# Az_Proj.net
KiCad netlist of a schematic drawn in Altium Designer
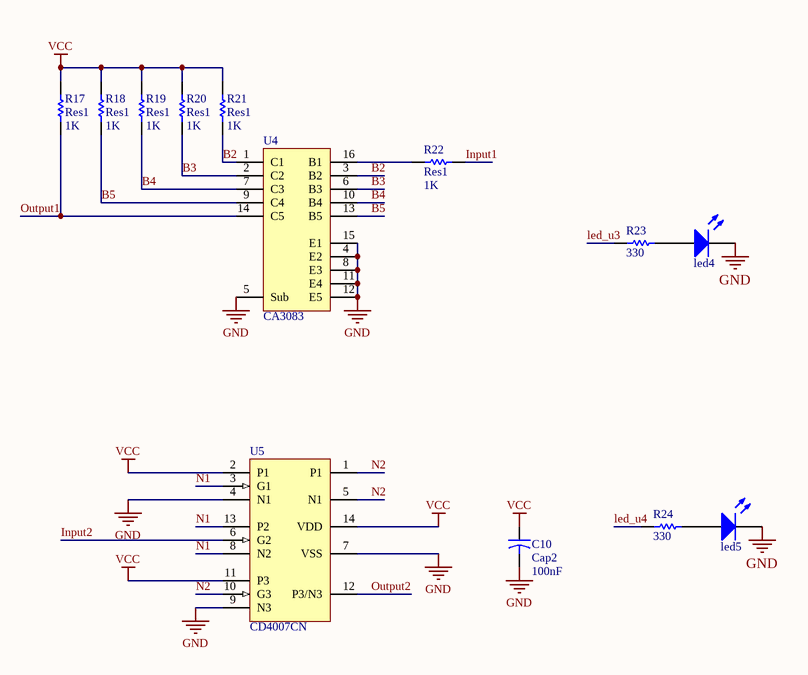
[diagram p0: Az_Proj.SchDoc]

(export (version "E")
  (design (tool "Eeschema 10.0.6"))
  (components
    (comp (ref "C10")
      (value "Cap2")
      (footprint "My_cap100n")
      (description "Capacitor")
      (fields (field (name "ALTIUM_VALUE") "100nF") (field (name "PUBLISHER") "Altium Limited"))
      (libsource (lib "Miscellaneous Devices") (part "Cap2"))
    )
    (comp (ref "led4")
      (value "LED 5mm")
      (footprint "Mine-Discreet:LED-5mm")
      (description "Typical LED")
      (fields (field (name "DESIGNER") "Seyed Mohsen Ghasemian") (field (name "PUBLISHER") "www.picpars.com"))
      (libsource (lib "PicPars.com_usefully_Library") (part "LED 5mm"))
    )
    (comp (ref "led5")
      (value "LED 5mm")
      (footprint "Mine-Discreet:LED-5mm")
      (description "Typical LED")
      (fields (field (name "DESIGNER") "Seyed Mohsen Ghasemian") (field (name "PUBLISHER") "www.picpars.com"))
      (libsource (lib "PicPars.com_usefully_Library") (part "LED 5mm"))
    )
    (comp (ref "R17")
      (value "Res1")
      (footprint "AXIAL-0.3")
      (description "Resistor")
      (fields (field (name "ALTIUM_VALUE") "1K") (field (name "PUBLISHER") "Altium Limited"))
      (libsource (lib "Miscellaneous Devices") (part "Res1"))
    )
    (comp (ref "R18")
      (value "Res1")
      (footprint "AXIAL-0.3")
      (description "Resistor")
      (fields (field (name "ALTIUM_VALUE") "1K") (field (name "PUBLISHER") "Altium Limited"))
      (libsource (lib "Miscellaneous Devices") (part "Res1"))
    )
    (comp (ref "R19")
      (value "Res1")
      (footprint "AXIAL-0.3")
      (description "Resistor")
      (fields (field (name "ALTIUM_VALUE") "1K") (field (name "PUBLISHER") "Altium Limited"))
      (libsource (lib "Miscellaneous Devices") (part "Res1"))
    )
    (comp (ref "R20")
      (value "Res1")
      (footprint "AXIAL-0.3")
      (description "Resistor")
      (fields (field (name "ALTIUM_VALUE") "1K") (field (name "PUBLISHER") "Altium Limited"))
      (libsource (lib "Miscellaneous Devices") (part "Res1"))
    )
    (comp (ref "R21")
      (value "Res1")
      (footprint "AXIAL-0.3")
      (description "Resistor")
      (fields (field (name "ALTIUM_VALUE") "1K") (field (name "PUBLISHER") "Altium Limited"))
      (libsource (lib "Miscellaneous Devices") (part "Res1"))
    )
    (comp (ref "R22")
      (value "Res1")
      (footprint "AXIAL-0.3")
      (description "Resistor")
      (fields (field (name "ALTIUM_VALUE") "1K") (field (name "PUBLISHER") "Altium Limited"))
      (libsource (lib "Miscellaneous Devices") (part "Res1"))
    )
    (comp (ref "R23")
      (value "330")
      (footprint "AXIAL-0.3")
      (description "Resistor")
      (fields (field (name "Comment") "Res1") (field (name "PUBLISHER") "Altium Limited"))
      (libsource (lib "Miscellaneous Devices") (part "Res1"))
    )
    (comp (ref "R24")
      (value "330")
      (footprint "AXIAL-0.3")
      (description "Resistor")
      (fields (field (name "Comment") "Res1") (field (name "PUBLISHER") "Altium Limited"))
      (libsource (lib "Miscellaneous Devices") (part "Res1"))
    )
    (comp (ref "U4") (value "CA3083") (footprint "DIP16") (libsource (lib "Ahmad_Library") (part "CA3083")))
    (comp (ref "U5")
      (value "CD4007CN")
      (footprint "DIP14")
      (description "Dual Complementary Pair Plus Inverter")
      (fields (field (name "PUBLISHER") "Altium Limited"))
      (libsource (lib "FSC Logic Switch") (part "CD4007CN"))
    )
  )
  (nets
    (net (code "1") (name "/B2") (class "Default")
      (node (ref "R21") (pin "1") (pinfunction "1_1") (pintype "passive"))
      (node (ref "U4") (pin "1") (pinfunction "C1_1") (pintype "passive"))
      (node (ref "U4") (pin "3") (pinfunction "B2_3") (pintype "passive"))
    )
    (net (code "2") (name "/B3") (class "Default")
      (node (ref "R20") (pin "1") (pinfunction "1_1") (pintype "passive"))
      (node (ref "U4") (pin "2") (pinfunction "C2_2") (pintype "passive"))
      (node (ref "U4") (pin "6") (pinfunction "B3_6") (pintype "passive"))
    )
    (net (code "3") (name "/B4") (class "Default")
      (node (ref "R19") (pin "1") (pinfunction "1_1") (pintype "passive"))
      (node (ref "U4") (pin "10") (pinfunction "B4_10") (pintype "passive"))
      (node (ref "U4") (pin "7") (pinfunction "C3_7") (pintype "passive"))
    )
    (net (code "4") (name "/B5") (class "Default")
      (node (ref "R18") (pin "1") (pinfunction "1_1") (pintype "passive"))
      (node (ref "U4") (pin "13") (pinfunction "B5_13") (pintype "passive"))
      (node (ref "U4") (pin "9") (pinfunction "C4_9") (pintype "passive"))
    )
    (net (code "5") (name "/Input1") (class "Default")
      (node (ref "R22") (pin "2") (pinfunction "2_2") (pintype "passive"))
    )
    (net (code "6") (name "/Input2") (class "Default")
      (node (ref "U5") (pin "6") (pinfunction "G2_6") (pintype "input"))
    )
    (net (code "7") (name "/N1") (class "Default")
      (node (ref "U5") (pin "13") (pinfunction "P2_13") (pintype "passive"))
      (node (ref "U5") (pin "3") (pinfunction "G1_3") (pintype "input"))
      (node (ref "U5") (pin "8") (pinfunction "N2_8") (pintype "passive"))
    )
    (net (code "8") (name "/N2") (class "Default")
      (node (ref "U5") (pin "1") (pinfunction "P1_1") (pintype "passive"))
      (node (ref "U5") (pin "10") (pinfunction "G3_10") (pintype "input"))
      (node (ref "U5") (pin "5") (pinfunction "N1_5") (pintype "passive"))
    )
    (net (code "9") (name "/Output1") (class "Default")
      (node (ref "R17") (pin "1") (pinfunction "1_1") (pintype "passive"))
      (node (ref "U4") (pin "14") (pinfunction "C5_14") (pintype "passive"))
    )
    (net (code "10") (name "/Output2") (class "Default")
      (node (ref "U5") (pin "12") (pinfunction "P3/N3_12") (pintype "passive"))
    )
    (net (code "11") (name "/led_u3") (class "Default")
      (node (ref "R23") (pin "1") (pinfunction "1_1") (pintype "passive"))
    )
    (net (code "12") (name "/led_u4") (class "Default")
      (node (ref "R24") (pin "1") (pinfunction "1_1") (pintype "passive"))
    )
    (net (code "13") (name "GND") (class "Default")
      (node (ref "C10") (pin "2") (pinfunction "2_2") (pintype "passive"))
      (node (ref "U4") (pin "11") (pinfunction "E4_11") (pintype "passive"))
      (node (ref "U4") (pin "12") (pinfunction "E5_12") (pintype "passive"))
      (node (ref "U4") (pin "15") (pinfunction "E1_15") (pintype "passive"))
      (node (ref "U4") (pin "4") (pinfunction "E2_4") (pintype "passive"))
      (node (ref "U4") (pin "5") (pinfunction "Sub_5") (pintype "passive"))
      (node (ref "U4") (pin "8") (pinfunction "E3_8") (pintype "passive"))
      (node (ref "U5") (pin "4") (pinfunction "N1_4") (pintype "passive"))
      (node (ref "U5") (pin "7") (pinfunction "VSS_7") (pintype "power_in"))
      (node (ref "U5") (pin "9") (pinfunction "N3_9") (pintype "passive"))
      (node (ref "led4") (pin "2") (pinfunction "K_2") (pintype "passive"))
      (node (ref "led5") (pin "2") (pinfunction "K_2") (pintype "passive"))
    )
    (net (code "14") (name "Net-(U4-B1)") (class "Default")
      (node (ref "R22") (pin "1") (pinfunction "1_1") (pintype "passive"))
      (node (ref "U4") (pin "16") (pinfunction "B1_16") (pintype "passive"))
    )
    (net (code "15") (name "Net-(led4-A)") (class "Default")
      (node (ref "R23") (pin "2") (pinfunction "2_2") (pintype "passive"))
      (node (ref "led4") (pin "1") (pinfunction "A_1") (pintype "passive"))
    )
    (net (code "16") (name "Net-(led5-A)") (class "Default")
      (node (ref "R24") (pin "2") (pinfunction "2_2") (pintype "passive"))
      (node (ref "led5") (pin "1") (pinfunction "A_1") (pintype "passive"))
    )
    (net (code "17") (name "VCC") (class "Default")
      (node (ref "C10") (pin "1") (pinfunction "1_1") (pintype "passive"))
      (node (ref "R17") (pin "2") (pinfunction "2_2") (pintype "passive"))
      (node (ref "R18") (pin "2") (pinfunction "2_2") (pintype "passive"))
      (node (ref "R19") (pin "2") (pinfunction "2_2") (pintype "passive"))
      (node (ref "R20") (pin "2") (pinfunction "2_2") (pintype "passive"))
      (node (ref "R21") (pin "2") (pinfunction "2_2") (pintype "passive"))
      (node (ref "U5") (pin "11") (pinfunction "P3_11") (pintype "passive"))
      (node (ref "U5") (pin "14") (pinfunction "VDD_14") (pintype "power_in"))
      (node (ref "U5") (pin "2") (pinfunction "P1_2") (pintype "passive"))
    )
  )
)
